# MainBoard.net
KiCad netlist of a schematic drawn in Altium Designer
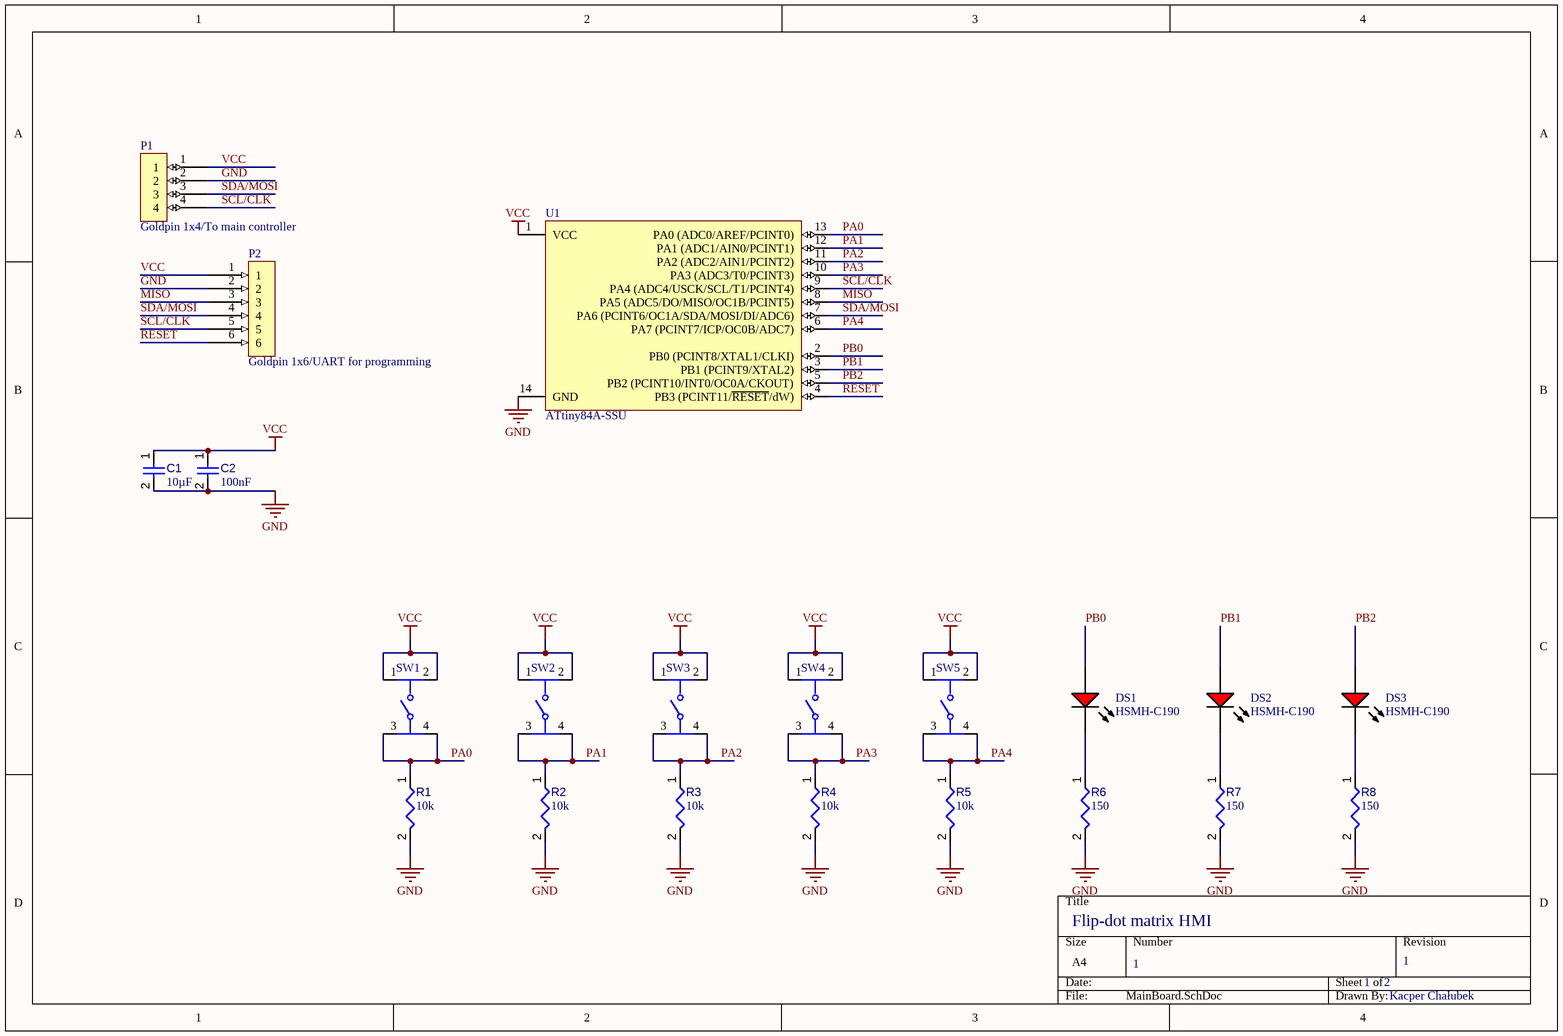
[diagram p0: MainBoard.SchDoc]

(export (version "E")
  (design (tool "Eeschema 10.0.6"))
  (components
    (comp (ref "C1")
      (value "10µF")
      (footprint "CAPC0603(1608)100_L")
      (description "Chip Capacitor, 10µF +/-20%, 10V, 0603, Thickness 1 mm")
      (fields (field (name "TOLERANCE") "10%") (field (name "Comment") "Capacitor 10µF +/-20% 10V 0603"))
      (libsource (lib "RWE") (part "CAP-NP-2"))
    )
    (comp (ref "C2")
      (value "100nF")
      (footprint "CAPC1608X90X40NL10T20")
      (description "Chip Capacitor, 100 nF, +/- 10%, 50 V, 0603 (1608 Metric)")
      (fields (field (name "TOLERANCE") "10%") (field (name "Comment") "Capacitor 100 nF +/-10% 50 V 0603"))
      (libsource (lib "RWE") (part "CAP-NP-2"))
    )
    (comp (ref "DS1")
      (value "HSMH-C190")
      (footprint "AVAG-HSMX-C190_V")
      (description "LED Uni-Color Red, 65 mW, 20 mA, -40 to 85 degC, 2-Pin SMD, RoHS, Tape and Reel")
      (fields (field (name "POWER") "78mW") (field (name "MANUFACTURER") "Avago"))
      (libsource (lib "RWE") (part "LED-RED-AK-2"))
    )
    (comp (ref "DS2")
      (value "HSMH-C190")
      (footprint "AVAG-HSMX-C190_V")
      (description "LED Uni-Color Red, 65 mW, 20 mA, -40 to 85 degC, 2-Pin SMD, RoHS, Tape and Reel")
      (fields (field (name "POWER") "78mW") (field (name "MANUFACTURER") "Avago"))
      (libsource (lib "RWE") (part "LED-RED-AK-2"))
    )
    (comp (ref "DS3")
      (value "HSMH-C190")
      (footprint "AVAG-HSMX-C190_V")
      (description "LED Uni-Color Red, 65 mW, 20 mA, -40 to 85 degC, 2-Pin SMD, RoHS, Tape and Reel")
      (fields (field (name "POWER") "78mW") (field (name "MANUFACTURER") "Avago"))
      (libsource (lib "RWE") (part "LED-RED-AK-2"))
    )
    (comp (ref "P1")
      (value "Goldpin 1x4/To main controller")
      (footprint "Goldpin 1x4-Footprint-1")
      (description "Goldpin, connector, 1 row 4 pin")
      (libsource (lib "RWE") (part "Goldpin 1x4-Symbol-1"))
    )
    (comp (ref "P2")
      (value "Goldpin 1x6/UART for programming")
      (footprint "Goldpin 1x6-Footprint-1")
      (description "Goldpin, connector, 1 row 6 pin")
      (libsource (lib "RWE") (part "Goldpin 1x6-Symbol-1"))
    )
    (comp (ref "R1")
      (value "10k")
      (footprint "RESC2013X50X35ML15T15")
      (description "Chip Resistor, 10 KOhm, +/- 1%, 125 mW, -55 to 155 degC, 0805 (2012 Metric)")
      (fields (field (name "TOLERANCE") "1%") (field (name "POWER") "125mW"))
      (libsource (lib "RWE") (part "RES-2"))
    )
    (comp (ref "R2")
      (value "10k")
      (footprint "RESC2013X50X35ML15T15")
      (description "Chip Resistor, 10 KOhm, +/- 1%, 125 mW, -55 to 155 degC, 0805 (2012 Metric)")
      (fields (field (name "TOLERANCE") "1%") (field (name "POWER") "125mW"))
      (libsource (lib "RWE") (part "RES-2"))
    )
    (comp (ref "R3")
      (value "10k")
      (footprint "RESC2013X50X35ML15T15")
      (description "Chip Resistor, 10 KOhm, +/- 1%, 125 mW, -55 to 155 degC, 0805 (2012 Metric)")
      (fields (field (name "TOLERANCE") "1%") (field (name "POWER") "125mW"))
      (libsource (lib "RWE") (part "RES-2"))
    )
    (comp (ref "R4")
      (value "10k")
      (footprint "RESC2013X50X35ML15T15")
      (description "Chip Resistor, 10 KOhm, +/- 1%, 125 mW, -55 to 155 degC, 0805 (2012 Metric)")
      (fields (field (name "TOLERANCE") "1%") (field (name "POWER") "125mW"))
      (libsource (lib "RWE") (part "RES-2"))
    )
    (comp (ref "R5")
      (value "10k")
      (footprint "RESC2013X50X35ML15T15")
      (description "Chip Resistor, 10 KOhm, +/- 1%, 125 mW, -55 to 155 degC, 0805 (2012 Metric)")
      (fields (field (name "TOLERANCE") "1%") (field (name "POWER") "125mW"))
      (libsource (lib "RWE") (part "RES-2"))
    )
    (comp (ref "R6")
      (value "150")
      (footprint "RESC2013X50X35ML15T15")
      (description "Chip Resistor, 10 KOhm, +/- 1%, 125 mW, -55 to 155 degC, 0805 (2012 Metric)")
      (fields (field (name "TOLERANCE") "1%") (field (name "POWER") "125mW"))
      (libsource (lib "RWE") (part "RES-2"))
    )
    (comp (ref "R7")
      (value "150")
      (footprint "RESC2013X50X35ML15T15")
      (description "Chip Resistor, 10 KOhm, +/- 1%, 125 mW, -55 to 155 degC, 0805 (2012 Metric)")
      (fields (field (name "TOLERANCE") "1%") (field (name "POWER") "125mW"))
      (libsource (lib "RWE") (part "RES-2"))
    )
    (comp (ref "R8")
      (value "150")
      (footprint "RESC2013X50X35ML15T15")
      (description "Chip Resistor, 10 KOhm, +/- 1%, 125 mW, -55 to 155 degC, 0805 (2012 Metric)")
      (fields (field (name "TOLERANCE") "1%") (field (name "POWER") "125mW"))
      (libsource (lib "RWE") (part "RES-2"))
    )
    (comp (ref "SW1")
      (value "PTS645SM43SMTR92LFS")
      (footprint "FP-PTS645SM43SMTR92LFS-MFG")
      (description "SWITCH TACTILE SPST-NO 0.05A 12V")
      (libsource (lib "Altium Content Vault") (part "1adf0dd01260c80cf25a44bfd6b99ba"))
    )
    (comp (ref "SW2")
      (value "PTS645SM43SMTR92LFS")
      (footprint "FP-PTS645SM43SMTR92LFS-MFG")
      (description "SWITCH TACTILE SPST-NO 0.05A 12V")
      (libsource (lib "Altium Content Vault") (part "1adf0dd01260c80cf25a44bfd6b99ba"))
    )
    (comp (ref "SW3")
      (value "PTS645SM43SMTR92LFS")
      (footprint "FP-PTS645SM43SMTR92LFS-MFG")
      (description "SWITCH TACTILE SPST-NO 0.05A 12V")
      (libsource (lib "Altium Content Vault") (part "1adf0dd01260c80cf25a44bfd6b99ba"))
    )
    (comp (ref "SW4")
      (value "PTS645SM43SMTR92LFS")
      (footprint "FP-PTS645SM43SMTR92LFS-MFG")
      (description "SWITCH TACTILE SPST-NO 0.05A 12V")
      (libsource (lib "Altium Content Vault") (part "1adf0dd01260c80cf25a44bfd6b99ba"))
    )
    (comp (ref "SW5")
      (value "PTS645SM43SMTR92LFS")
      (footprint "FP-PTS645SM43SMTR92LFS-MFG")
      (description "SWITCH TACTILE SPST-NO 0.05A 12V")
      (libsource (lib "Altium Content Vault") (part "1adf0dd01260c80cf25a44bfd6b99ba"))
    )
    (comp (ref "U1")
      (value "ATtiny84A-SSU")
      (footprint "14S1_M")
      (libsource (lib "Altium Content Vault") (part "MC-8B-ATTINY24V-IL14"))
    )
  )
  (nets
    (net (code "1") (name "/MISO") (class "Default")
      (node (ref "P2") (pin "3") (pinfunction "3_3") (pintype "input"))
      (node (ref "U1") (pin "8") (pinfunction "PA5_(ADC5/DO/MISO/OC1B/PCINT5)_8") (pintype "bidirectional"))
    )
    (net (code "2") (name "/PA0") (class "Default")
      (node (ref "R1") (pin "1") (pinfunction "1_1") (pintype "passive"))
      (node (ref "SW1") (pin "3") (pinfunction "3_3") (pintype "passive"))
      (node (ref "SW1") (pin "4") (pinfunction "4_4") (pintype "passive"))
      (node (ref "U1") (pin "13") (pinfunction "PA0_(ADC0/AREF/PCINT0)_13") (pintype "bidirectional"))
    )
    (net (code "3") (name "/PA1") (class "Default")
      (node (ref "R2") (pin "1") (pinfunction "1_1") (pintype "passive"))
      (node (ref "SW2") (pin "3") (pinfunction "3_3") (pintype "passive"))
      (node (ref "SW2") (pin "4") (pinfunction "4_4") (pintype "passive"))
      (node (ref "U1") (pin "12") (pinfunction "PA1_(ADC1/AIN0/PCINT1)_12") (pintype "bidirectional"))
    )
    (net (code "4") (name "/PA2") (class "Default")
      (node (ref "R3") (pin "1") (pinfunction "1_1") (pintype "passive"))
      (node (ref "SW3") (pin "3") (pinfunction "3_3") (pintype "passive"))
      (node (ref "SW3") (pin "4") (pinfunction "4_4") (pintype "passive"))
      (node (ref "U1") (pin "11") (pinfunction "PA2_(ADC2/AIN1/PCINT2)_11") (pintype "bidirectional"))
    )
    (net (code "5") (name "/PA3") (class "Default")
      (node (ref "R4") (pin "1") (pinfunction "1_1") (pintype "passive"))
      (node (ref "SW4") (pin "3") (pinfunction "3_3") (pintype "passive"))
      (node (ref "SW4") (pin "4") (pinfunction "4_4") (pintype "passive"))
      (node (ref "U1") (pin "10") (pinfunction "PA3_(ADC3/T0/PCINT3)_10") (pintype "bidirectional"))
    )
    (net (code "6") (name "/PA4") (class "Default")
      (node (ref "R5") (pin "1") (pinfunction "1_1") (pintype "passive"))
      (node (ref "SW5") (pin "3") (pinfunction "3_3") (pintype "passive"))
      (node (ref "SW5") (pin "4") (pinfunction "4_4") (pintype "passive"))
      (node (ref "U1") (pin "6") (pinfunction "PA7_(PCINT7/ICP/OC0B/ADC7)_6") (pintype "bidirectional"))
    )
    (net (code "7") (name "/PB0") (class "Default")
      (node (ref "DS1") (pin "1") (pinfunction "A_1") (pintype "passive"))
      (node (ref "U1") (pin "2") (pinfunction "PB0_(PCINT8/XTAL1/CLKI)_2") (pintype "bidirectional"))
    )
    (net (code "8") (name "/PB1") (class "Default")
      (node (ref "DS2") (pin "1") (pinfunction "A_1") (pintype "passive"))
      (node (ref "U1") (pin "3") (pinfunction "PB1_(PCINT9/XTAL2)_3") (pintype "bidirectional"))
    )
    (net (code "9") (name "/PB2") (class "Default")
      (node (ref "DS3") (pin "1") (pinfunction "A_1") (pintype "passive"))
      (node (ref "U1") (pin "5") (pinfunction "PB2_(PCINT10/INT0/OC0A/CKOUT)_5") (pintype "bidirectional"))
    )
    (net (code "10") (name "/RESET") (class "Default")
      (node (ref "P2") (pin "6") (pinfunction "6_6") (pintype "input"))
      (node (ref "U1") (pin "4") (pinfunction "PB3_(PCINT11/~{RESET}/dW)_4") (pintype "bidirectional"))
    )
    (net (code "11") (name "/SCL{slash}CLK") (class "Default")
      (node (ref "P1") (pin "4") (pinfunction "4_4") (pintype "bidirectional"))
      (node (ref "P2") (pin "5") (pinfunction "5_5") (pintype "input"))
      (node (ref "U1") (pin "9") (pinfunction "PA4_(ADC4/USCK/SCL/T1/PCINT4)_9") (pintype "bidirectional"))
    )
    (net (code "12") (name "/SDA{slash}MOSI") (class "Default")
      (node (ref "P1") (pin "3") (pinfunction "3_3") (pintype "bidirectional"))
      (node (ref "P2") (pin "4") (pinfunction "4_4") (pintype "input"))
      (node (ref "U1") (pin "7") (pinfunction "PA6_(PCINT6/OC1A/SDA/MOSI/DI/ADC6)_7") (pintype "bidirectional"))
    )
    (net (code "13") (name "GND") (class "Default")
      (node (ref "C1") (pin "2") (pinfunction "2_2") (pintype "passive"))
      (node (ref "C2") (pin "2") (pinfunction "2_2") (pintype "passive"))
      (node (ref "P1") (pin "2") (pinfunction "2_2") (pintype "bidirectional"))
      (node (ref "P2") (pin "2") (pinfunction "2_2") (pintype "input"))
      (node (ref "R1") (pin "2") (pinfunction "2_2") (pintype "passive"))
      (node (ref "R2") (pin "2") (pinfunction "2_2") (pintype "passive"))
      (node (ref "R3") (pin "2") (pinfunction "2_2") (pintype "passive"))
      (node (ref "R4") (pin "2") (pinfunction "2_2") (pintype "passive"))
      (node (ref "R5") (pin "2") (pinfunction "2_2") (pintype "passive"))
      (node (ref "R6") (pin "2") (pinfunction "2_2") (pintype "passive"))
      (node (ref "R7") (pin "2") (pinfunction "2_2") (pintype "passive"))
      (node (ref "R8") (pin "2") (pinfunction "2_2") (pintype "passive"))
      (node (ref "U1") (pin "14") (pinfunction "GND_14") (pintype "power_in"))
    )
    (net (code "14") (name "Net-(DS1-K)") (class "Default")
      (node (ref "DS1") (pin "2") (pinfunction "K_2") (pintype "passive"))
      (node (ref "R6") (pin "1") (pinfunction "1_1") (pintype "passive"))
    )
    (net (code "15") (name "Net-(DS2-K)") (class "Default")
      (node (ref "DS2") (pin "2") (pinfunction "K_2") (pintype "passive"))
      (node (ref "R7") (pin "1") (pinfunction "1_1") (pintype "passive"))
    )
    (net (code "16") (name "Net-(DS3-K)") (class "Default")
      (node (ref "DS3") (pin "2") (pinfunction "K_2") (pintype "passive"))
      (node (ref "R8") (pin "1") (pinfunction "1_1") (pintype "passive"))
    )
    (net (code "17") (name "VCC") (class "Default")
      (node (ref "C1") (pin "1") (pinfunction "1_1") (pintype "passive"))
      (node (ref "C2") (pin "1") (pinfunction "1_1") (pintype "passive"))
      (node (ref "P1") (pin "1") (pinfunction "1_1") (pintype "bidirectional"))
      (node (ref "P2") (pin "1") (pinfunction "1_1") (pintype "input"))
      (node (ref "SW1") (pin "1") (pinfunction "1_1") (pintype "passive"))
      (node (ref "SW1") (pin "2") (pinfunction "2_2") (pintype "passive"))
      (node (ref "SW2") (pin "1") (pinfunction "1_1") (pintype "passive"))
      (node (ref "SW2") (pin "2") (pinfunction "2_2") (pintype "passive"))
      (node (ref "SW3") (pin "1") (pinfunction "1_1") (pintype "passive"))
      (node (ref "SW3") (pin "2") (pinfunction "2_2") (pintype "passive"))
      (node (ref "SW4") (pin "1") (pinfunction "1_1") (pintype "passive"))
      (node (ref "SW4") (pin "2") (pinfunction "2_2") (pintype "passive"))
      (node (ref "SW5") (pin "1") (pinfunction "1_1") (pintype "passive"))
      (node (ref "SW5") (pin "2") (pinfunction "2_2") (pintype "passive"))
      (node (ref "U1") (pin "1") (pinfunction "VCC_1") (pintype "power_in"))
    )
  )
)
